# FPGA_PERIPHERALS.net
KiCad netlist of a schematic drawn in Altium Designer
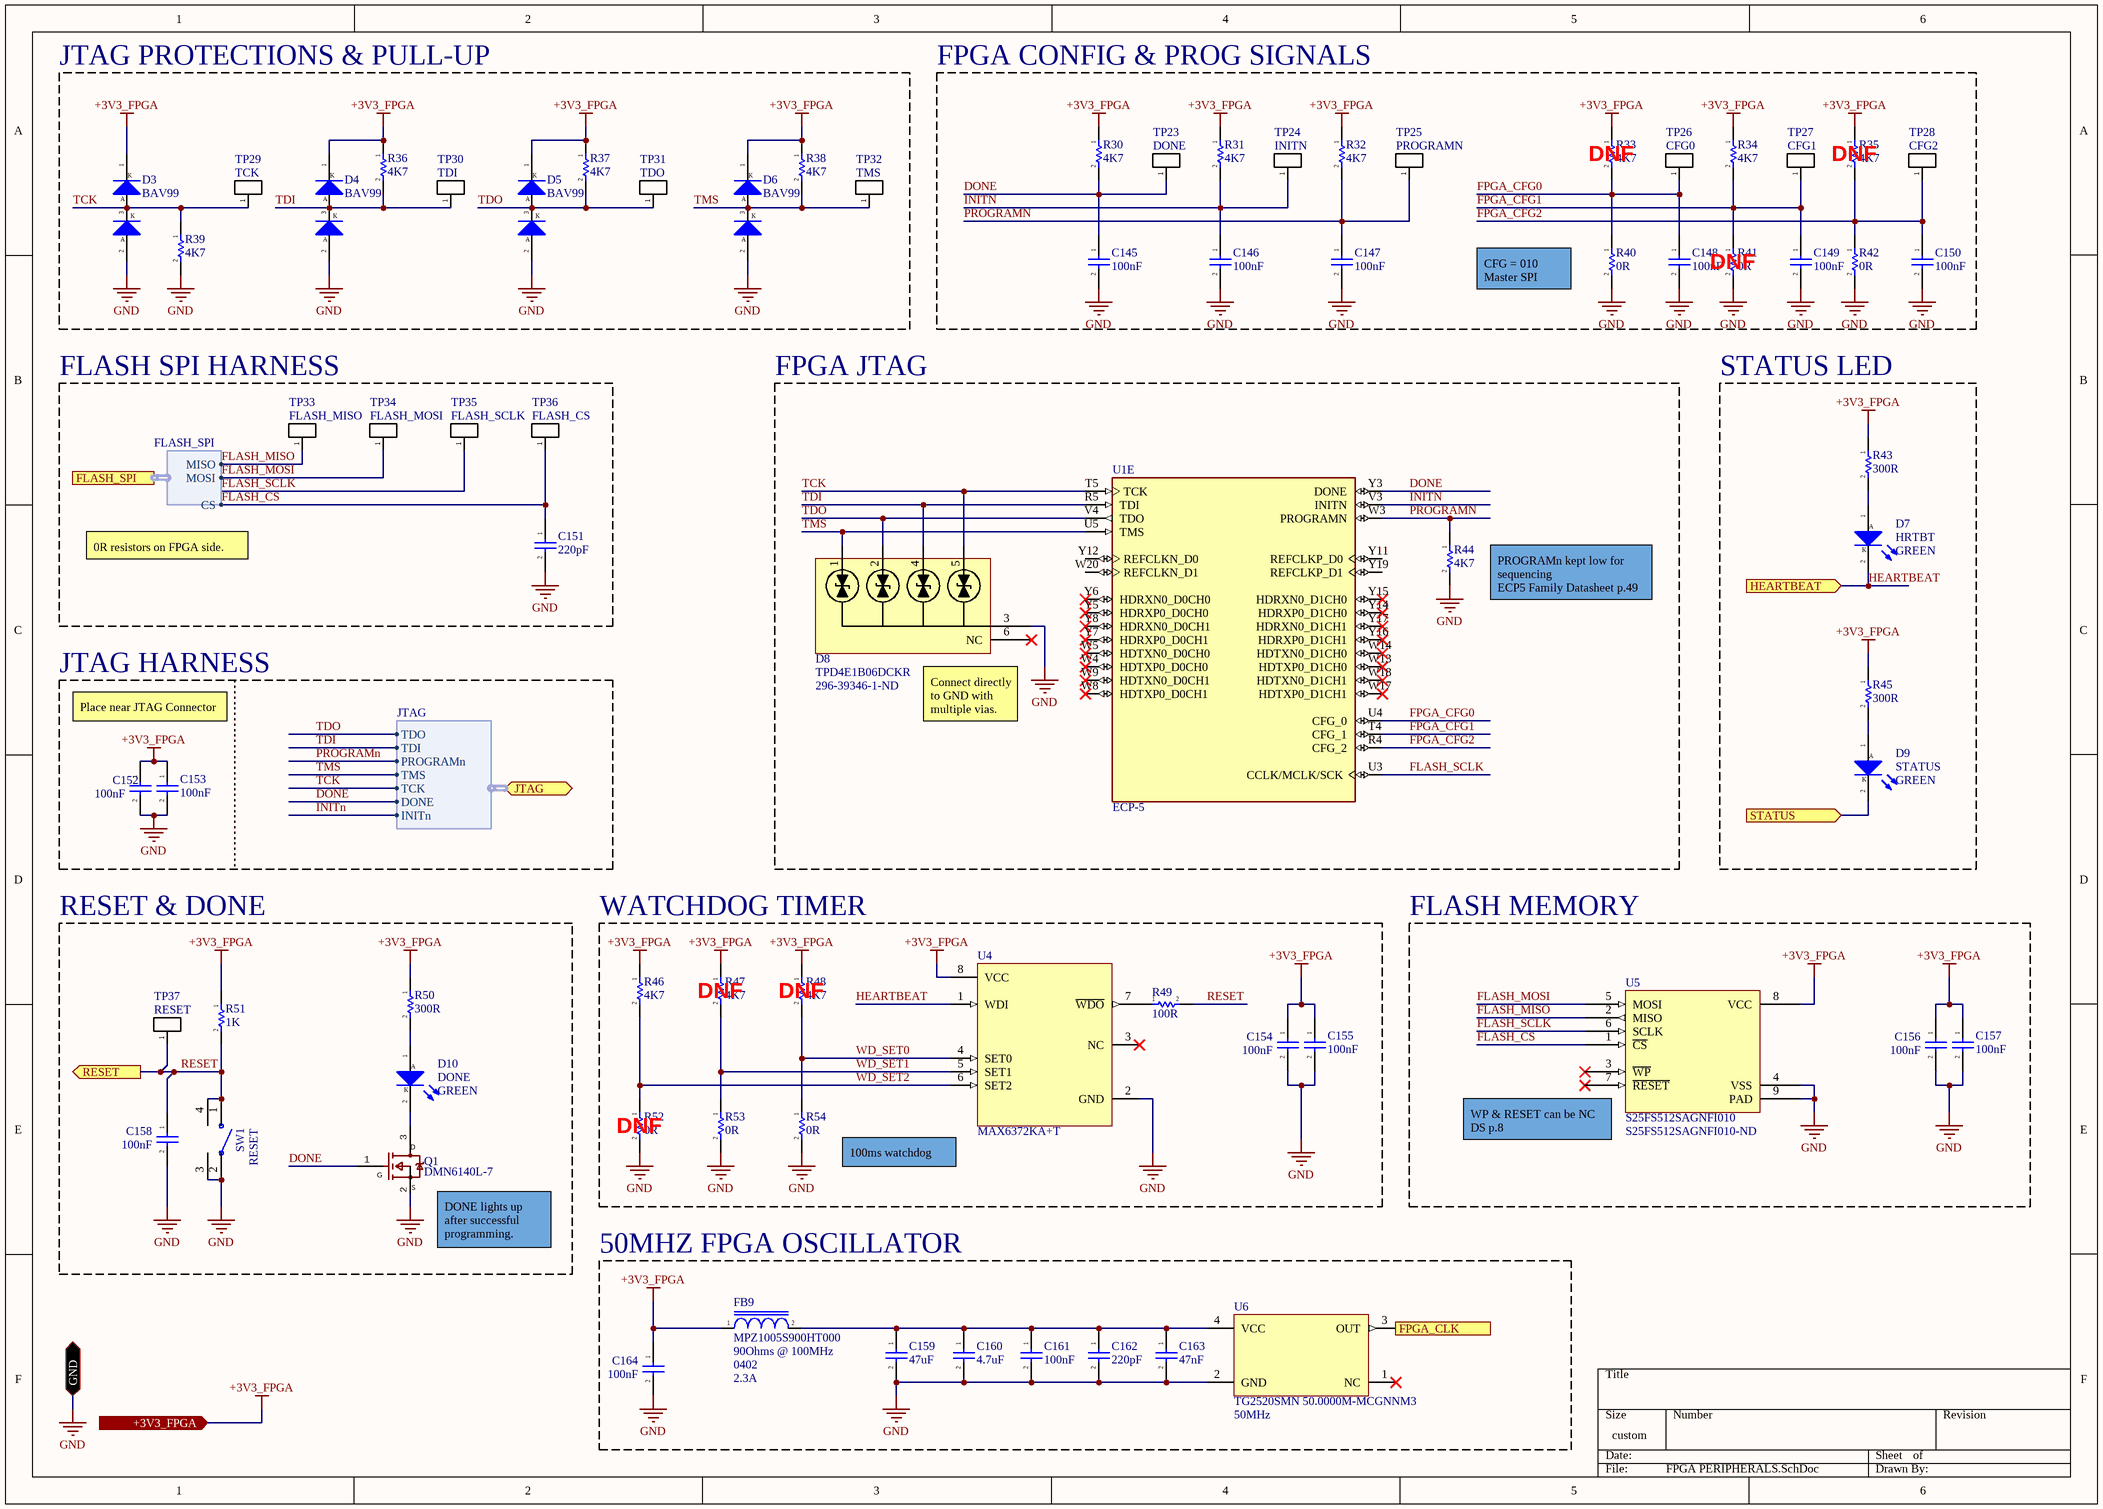
[diagram p0: FPGA PERIPHERALS.SchDoc]

(export (version "E")
  (design (tool "Eeschema 10.0.6"))
  (components
    (comp (ref "C145")
      (value "100nF")
      (footprint "CAP_0402")
      (description "Generic SMT Ceramic Capacitor")
      (libsource (lib "Symbols") (part "CAP_CER"))
    )
    (comp (ref "C146")
      (value "100nF")
      (footprint "CAP_0402")
      (description "Generic SMT Ceramic Capacitor")
      (libsource (lib "Symbols") (part "CAP_CER"))
    )
    (comp (ref "C147")
      (value "100nF")
      (footprint "CAP_0402")
      (description "Generic SMT Ceramic Capacitor")
      (libsource (lib "Symbols") (part "CAP_CER"))
    )
    (comp (ref "C148")
      (value "100nF")
      (footprint "CAP_0402")
      (description "Generic SMT Ceramic Capacitor")
      (libsource (lib "Symbols") (part "CAP_CER"))
    )
    (comp (ref "C149")
      (value "100nF")
      (footprint "CAP_0402")
      (description "Generic SMT Ceramic Capacitor")
      (libsource (lib "Symbols") (part "CAP_CER"))
    )
    (comp (ref "C150")
      (value "100nF")
      (footprint "CAP_0402")
      (description "Generic SMT Ceramic Capacitor")
      (libsource (lib "Symbols") (part "CAP_CER"))
    )
    (comp (ref "C151")
      (value "220pF")
      (footprint "CAP_0402")
      (description "Generic SMT Ceramic Capacitor")
      (libsource (lib "Symbols") (part "CAP_CER"))
    )
    (comp (ref "C152")
      (value "100nF")
      (footprint "CAP_0402")
      (description "Generic SMT Ceramic Capacitor")
      (libsource (lib "Symbols") (part "CAP_CER"))
    )
    (comp (ref "C153")
      (value "100nF")
      (footprint "CAP_0402")
      (description "Generic SMT Ceramic Capacitor")
      (libsource (lib "Symbols") (part "CAP_CER"))
    )
    (comp (ref "C154")
      (value "100nF")
      (footprint "CAP_0402")
      (description "Generic SMT Ceramic Capacitor")
      (libsource (lib "Symbols") (part "CAP_CER"))
    )
    (comp (ref "C155")
      (value "100nF")
      (footprint "CAP_0402")
      (description "Generic SMT Ceramic Capacitor")
      (libsource (lib "Symbols") (part "CAP_CER"))
    )
    (comp (ref "C156")
      (value "100nF")
      (footprint "CAP_0402")
      (description "Generic SMT Ceramic Capacitor")
      (libsource (lib "Symbols") (part "CAP_CER"))
    )
    (comp (ref "C157")
      (value "100nF")
      (footprint "CAP_0402")
      (description "Generic SMT Ceramic Capacitor")
      (libsource (lib "Symbols") (part "CAP_CER"))
    )
    (comp (ref "C158")
      (value "100nF")
      (footprint "CAP_0402")
      (description "Generic SMT Ceramic Capacitor")
      (libsource (lib "Symbols") (part "CAP_CER"))
    )
    (comp (ref "C159")
      (value "47uF")
      (footprint "CAP_1206")
      (description "Generic SMT Ceramic Capacitor")
      (libsource (lib "Symbols") (part "CAP_CER"))
    )
    (comp (ref "C160")
      (value "4.7uF")
      (footprint "CAP_0805")
      (description "Generic SMT Ceramic Capacitor")
      (libsource (lib "Symbols") (part "CAP_CER"))
    )
    (comp (ref "C161")
      (value "100nF")
      (footprint "CAP_0402")
      (description "Generic SMT Ceramic Capacitor")
      (libsource (lib "Symbols") (part "CAP_CER"))
    )
    (comp (ref "C162")
      (value "220pF")
      (footprint "CAP_0402")
      (description "Generic SMT Ceramic Capacitor")
      (libsource (lib "Symbols") (part "CAP_CER"))
    )
    (comp (ref "C163")
      (value "47nF")
      (footprint "CAP_0201")
      (description "Generic SMT Ceramic Capacitor")
      (libsource (lib "Symbols") (part "CAP_CER"))
    )
    (comp (ref "C164")
      (value "100nF")
      (footprint "CAP_0402")
      (description "Generic SMT Ceramic Capacitor")
      (libsource (lib "Symbols") (part "CAP_CER"))
    )
    (comp (ref "D3")
      (value "BAV99")
      (footprint "MMBD7000-7-F")
      (description "DIODE ARRAY GP 75V 300MA SOT23-3")
      (fields (field (name "MFR") "Taiwan Semiconductor Corporation"))
      (libsource (lib "CryptLib") (part "DIODE_BAV99"))
    )
    (comp (ref "D4")
      (value "BAV99")
      (footprint "MMBD7000-7-F")
      (description "DIODE ARRAY GP 75V 300MA SOT23-3")
      (fields (field (name "MFR") "Taiwan Semiconductor Corporation"))
      (libsource (lib "CryptLib") (part "DIODE_BAV99"))
    )
    (comp (ref "D5")
      (value "BAV99")
      (footprint "MMBD7000-7-F")
      (description "DIODE ARRAY GP 75V 300MA SOT23-3")
      (fields (field (name "MFR") "Taiwan Semiconductor Corporation"))
      (libsource (lib "CryptLib") (part "DIODE_BAV99"))
    )
    (comp (ref "D6")
      (value "BAV99")
      (footprint "MMBD7000-7-F")
      (description "DIODE ARRAY GP 75V 300MA SOT23-3")
      (fields (field (name "MFR") "Taiwan Semiconductor Corporation"))
      (libsource (lib "CryptLib") (part "DIODE_BAV99"))
    )
    (comp (ref "D7")
      (value "HRTBT")
      (footprint "LED_0402")
      (description "Generic LED")
      (fields (field (name "COLOR") "GREEN"))
      (libsource (lib "RaesLib") (part "DIODE_LED"))
    )
    (comp (ref "D8")
      (value "TPD4E1B06DCKR")
      (footprint "TPD4E1B06DCKR")
      (description "TVS DIODE 5.5VWM 14.5VC SC70-6")
      (fields
        (field (name "MFR") "Texas Instruments")
        (field (name "SUPPLIER PART NUMBER 1") "296-39346-1-ND")
      )
      (libsource (lib "CryptLib") (part "DIODE_TPD4E1B06DCKR"))
    )
    (comp (ref "D9")
      (value "STATUS")
      (footprint "LED_0402")
      (description "Generic LED")
      (fields (field (name "COLOR") "GREEN"))
      (libsource (lib "RaesLib") (part "DIODE_LED"))
    )
    (comp (ref "D10")
      (value "DONE")
      (footprint "LED_0402")
      (description "Generic LED")
      (fields (field (name "COLOR") "GREEN"))
      (libsource (lib "RaesLib") (part "DIODE_LED"))
    )
    (comp (ref "FB9")
      (value "MPZ1005S900HT000")
      (footprint "IND_0402")
      (description "90 Ohms @ 100 MHz 1 Power Line Ferrite Bead 0402 (1005 Metric) 2.3A 38mOhm")
      (fields
        (field (name "IMPEDANCE @ FREQ") "90Ohms @ 100MHz")
        (field (name "PACKAGE / CASE") "0402")
        (field (name "CURRENT RATING") "2.3A")
      )
      (libsource (lib "CryptLib") (part "IND_MPZ1005S900HT000"))
    )
    (comp (ref "Q1")
      (value "DMN6140L-7")
      (footprint "SOT23-3")
      (description "N-Channel 60 V 1.6A (Ta) 700mW (Ta) Surface Mount SOT-23")
      (fields (field (name "MFR") "Diodes Incorporated"))
      (libsource (lib "CryptLib") (part "TRANS_DMN6140L-7"))
    )
    (comp (ref "R30")
      (value "4K7")
      (footprint "RES_0603")
      (description "Resistor")
      (fields (field (name "POWER") "1/16W") (field (name "TOLERANCE") "10%"))
      (libsource (lib "Symbols") (part "RESISTOR"))
    )
    (comp (ref "R31")
      (value "4K7")
      (footprint "RES_0603")
      (description "Resistor")
      (fields (field (name "POWER") "1/16W") (field (name "TOLERANCE") "10%"))
      (libsource (lib "Symbols") (part "RESISTOR"))
    )
    (comp (ref "R32")
      (value "4K7")
      (footprint "RES_0603")
      (description "Resistor")
      (fields (field (name "POWER") "1/16W") (field (name "TOLERANCE") "10%"))
      (libsource (lib "Symbols") (part "RESISTOR"))
    )
    (comp (ref "R33")
      (value "4K7")
      (footprint "RES_0603")
      (description "Resistor")
      (fields (field (name "POWER") "1/16W") (field (name "TOLERANCE") "10%"))
      (libsource (lib "Symbols") (part "RESISTOR"))
    )
    (comp (ref "R34")
      (value "4K7")
      (footprint "RES_0603")
      (description "Resistor")
      (fields (field (name "POWER") "1/16W") (field (name "TOLERANCE") "10%"))
      (libsource (lib "Symbols") (part "RESISTOR"))
    )
    (comp (ref "R35")
      (value "4K7")
      (footprint "RES_0603")
      (description "Resistor")
      (fields (field (name "POWER") "1/16W") (field (name "TOLERANCE") "10%"))
      (libsource (lib "Symbols") (part "RESISTOR"))
    )
    (comp (ref "R36")
      (value "4K7")
      (footprint "RES_0603")
      (description "Resistor")
      (fields (field (name "POWER") "1/16W") (field (name "TOLERANCE") "10%"))
      (libsource (lib "Symbols") (part "RESISTOR"))
    )
    (comp (ref "R37")
      (value "4K7")
      (footprint "RES_0603")
      (description "Resistor")
      (fields (field (name "POWER") "1/16W") (field (name "TOLERANCE") "10%"))
      (libsource (lib "Symbols") (part "RESISTOR"))
    )
    (comp (ref "R38")
      (value "4K7")
      (footprint "RES_0603")
      (description "Resistor")
      (fields (field (name "POWER") "1/16W") (field (name "TOLERANCE") "10%"))
      (libsource (lib "Symbols") (part "RESISTOR"))
    )
    (comp (ref "R39")
      (value "4K7")
      (footprint "RES_0603")
      (description "Resistor")
      (fields (field (name "POWER") "1/16W") (field (name "TOLERANCE") "10%"))
      (libsource (lib "Symbols") (part "RESISTOR"))
    )
    (comp (ref "R40")
      (value "0R")
      (footprint "RES_0603")
      (description "Resistor")
      (fields (field (name "POWER") "1/8W") (field (name "TOLERANCE") "10%"))
      (libsource (lib "Symbols") (part "RESISTOR"))
    )
    (comp (ref "R41")
      (value "0R")
      (footprint "RES_0603")
      (description "Resistor")
      (fields (field (name "POWER") "1/8W") (field (name "TOLERANCE") "10%"))
      (libsource (lib "Symbols") (part "RESISTOR"))
    )
    (comp (ref "R42")
      (value "0R")
      (footprint "RES_0603")
      (description "Resistor")
      (fields (field (name "POWER") "1/8W") (field (name "TOLERANCE") "10%"))
      (libsource (lib "Symbols") (part "RESISTOR"))
    )
    (comp (ref "R43")
      (value "300R")
      (footprint "RES_0603")
      (description "Resistor")
      (fields (field (name "POWER") "1/8W") (field (name "TOLERANCE") "2%"))
      (libsource (lib "Symbols") (part "RESISTOR"))
    )
    (comp (ref "R44")
      (value "4K7")
      (footprint "RES_0603")
      (description "Resistor")
      (fields (field (name "POWER") "1/16W") (field (name "TOLERANCE") "10%"))
      (libsource (lib "Symbols") (part "RESISTOR"))
    )
    (comp (ref "R45")
      (value "300R")
      (footprint "RES_0603")
      (description "Resistor")
      (fields (field (name "POWER") "1/8W") (field (name "TOLERANCE") "2%"))
      (libsource (lib "Symbols") (part "RESISTOR"))
    )
    (comp (ref "R46")
      (value "4K7")
      (footprint "RES_0603")
      (description "Resistor")
      (fields (field (name "POWER") "1/16W") (field (name "TOLERANCE") "10%"))
      (libsource (lib "Symbols") (part "RESISTOR"))
    )
    (comp (ref "R47")
      (value "4K7")
      (footprint "RES_0603")
      (description "Resistor")
      (fields (field (name "POWER") "1/16W") (field (name "TOLERANCE") "10%"))
      (libsource (lib "Symbols") (part "RESISTOR"))
    )
    (comp (ref "R48")
      (value "4K7")
      (footprint "RES_0603")
      (description "Resistor")
      (fields (field (name "POWER") "1/16W") (field (name "TOLERANCE") "10%"))
      (libsource (lib "Symbols") (part "RESISTOR"))
    )
    (comp (ref "R49")
      (value "100R")
      (footprint "RES_0402")
      (description "Resistor")
      (fields (field (name "POWER") "1/8W") (field (name "TOLERANCE") "10%"))
      (libsource (lib "Symbols") (part "RESISTOR"))
    )
    (comp (ref "R50")
      (value "300R")
      (footprint "RES_0603")
      (description "Resistor")
      (fields (field (name "POWER") "1/8W") (field (name "TOLERANCE") "2%"))
      (libsource (lib "Symbols") (part "RESISTOR"))
    )
    (comp (ref "R51")
      (value "1K")
      (footprint "RES_0603")
      (description "Resistor")
      (fields (field (name "POWER") "1/8W") (field (name "TOLERANCE") "5%"))
      (libsource (lib "Symbols") (part "RESISTOR"))
    )
    (comp (ref "R52")
      (value "0R")
      (footprint "RES_0603")
      (description "Resistor")
      (fields (field (name "POWER") "1/8W") (field (name "TOLERANCE") "10%"))
      (libsource (lib "Symbols") (part "RESISTOR"))
    )
    (comp (ref "R53")
      (value "0R")
      (footprint "RES_0603")
      (description "Resistor")
      (fields (field (name "POWER") "1/8W") (field (name "TOLERANCE") "10%"))
      (libsource (lib "Symbols") (part "RESISTOR"))
    )
    (comp (ref "R54")
      (value "0R")
      (footprint "RES_0603")
      (description "Resistor")
      (fields (field (name "POWER") "1/8W") (field (name "TOLERANCE") "10%"))
      (libsource (lib "Symbols") (part "RESISTOR"))
    )
    (comp (ref "SW1")
      (value "RESET")
      (footprint "KMR621NGLFS")
      (description "Tactile Switch SPST-NO Top Actuated Surface Mount")
      (fields (field (name "MFR") "C&K") (field (name "ALTERNATIVE PART") "KMR641NG ULC LFS"))
      (libsource (lib "CryptLib") (part "SW_KMR621NG_LFS"))
    )
    (comp (ref "TP23")
      (value "DONE")
      (footprint "TP_PAD_TINY")
      (description "Test Point")
      (libsource (lib "Symbols") (part "TESTPOINT"))
    )
    (comp (ref "TP24")
      (value "INITN")
      (footprint "TP_PAD_TINY")
      (description "Test Point")
      (libsource (lib "Symbols") (part "TESTPOINT"))
    )
    (comp (ref "TP25")
      (value "PROGRAMN")
      (footprint "TP_PAD_TINY")
      (description "Test Point")
      (libsource (lib "Symbols") (part "TESTPOINT"))
    )
    (comp (ref "TP26")
      (value "CFG0")
      (footprint "TP_PAD_TINY")
      (description "Test Point")
      (libsource (lib "Symbols") (part "TESTPOINT"))
    )
    (comp (ref "TP27")
      (value "CFG1")
      (footprint "TP_PAD_TINY")
      (description "Test Point")
      (libsource (lib "Symbols") (part "TESTPOINT"))
    )
    (comp (ref "TP28")
      (value "CFG2")
      (footprint "TP_PAD_TINY")
      (description "Test Point")
      (libsource (lib "Symbols") (part "TESTPOINT"))
    )
    (comp (ref "TP29")
      (value "TCK")
      (footprint "TP_PAD_SMALL")
      (description "Test Point")
      (libsource (lib "Symbols") (part "TESTPOINT"))
    )
    (comp (ref "TP30")
      (value "TDI")
      (footprint "TP_PAD_SMALL")
      (description "Test Point")
      (libsource (lib "Symbols") (part "TESTPOINT"))
    )
    (comp (ref "TP31")
      (value "TDO")
      (footprint "TP_PAD_SMALL")
      (description "Test Point")
      (libsource (lib "Symbols") (part "TESTPOINT"))
    )
    (comp (ref "TP32")
      (value "TMS")
      (footprint "TP_PAD_SMALL")
      (description "Test Point")
      (libsource (lib "Symbols") (part "TESTPOINT"))
    )
    (comp (ref "TP33")
      (value "FLASH_MISO")
      (footprint "TP_PAD_SMALL")
      (description "Test Point")
      (libsource (lib "Symbols") (part "TESTPOINT"))
    )
    (comp (ref "TP34")
      (value "FLASH_MOSI")
      (footprint "TP_PAD_SMALL")
      (description "Test Point")
      (libsource (lib "Symbols") (part "TESTPOINT"))
    )
    (comp (ref "TP35")
      (value "FLASH_SCLK")
      (footprint "TP_PAD_SMALL")
      (description "Test Point")
      (libsource (lib "Symbols") (part "TESTPOINT"))
    )
    (comp (ref "TP36")
      (value "FLASH_CS")
      (footprint "TP_PAD_SMALL")
      (description "Test Point")
      (libsource (lib "Symbols") (part "TESTPOINT"))
    )
    (comp (ref "TP37")
      (value "RESET")
      (footprint "TP_PAD_SMALL")
      (description "Test Point")
      (libsource (lib "Symbols") (part "TESTPOINT"))
    )
    (comp (ref "U1")
      (value "ECP-5")
      (footprint "CryptLib:CABGA-381")
      (description "IC FPGA 203 I/O 381CABGA")
      (fields (field (name "MFR") "Lattice Semiconductors"))
      (libsource (lib "CryptLib") (part "IC_LFE5UM-45F-8BG381C"))
    )
    (comp (ref "U4")
      (value "MAX6372KA+T")
      (footprint "SOT23-8")
      (description "Watchdog Push-Pull, Totem Pole 1 Channel SOT-23-8")
      (fields (field (name "MFR") "Maxim Integrated"))
      (libsource (lib "CryptLib") (part "IC_MAX6372KA-T"))
    )
    (comp (ref "U5")
      (value "S25FS512SAGNFI010")
      (footprint "s25FL256LAGNFV010")
      (description "FLASH - NOR Memory IC 512Mb (64M x 8) SPI - Quad I/O, QPI 133 MHz 8-WSON (6x8)")
      (fields (field (name "MFR") "Cypress") (field (name "SUPPLIER PART NUMBER 1") "S25FS512SAGNFI010-ND"))
      (libsource (lib "CryptLib") (part "IC_S25FS512SAGNFI010"))
    )
    (comp (ref "U6")
      (value "TG2520SMN 50.0000M-MCGNNM3")
      (footprint "TG2520SMN")
      (description "50 MHz TCXO Clipped Sine Wave Oscillator 2.8V ~ 3.3V - 4-SMD, No Lead")
      (fields (field (name "MFR") "EPSON") (field (name "FREQUENCY") "50MHz"))
      (libsource (lib "CryptLib") (part "IC_TG2520SMN_50.0000M-MCGNNM3"))
    )
  )
  (nets
    (net (code "3") (name "+3V3_FPGA") (class "Default")
      (node (ref "C152") (pin "1") (pinfunction "1_1") (pintype "passive"))
      (node (ref "C153") (pin "1") (pinfunction "1_1") (pintype "passive"))
      (node (ref "C154") (pin "1") (pinfunction "1_1") (pintype "passive"))
      (node (ref "C155") (pin "1") (pinfunction "1_1") (pintype "passive"))
      (node (ref "C156") (pin "1") (pinfunction "1_1") (pintype "passive"))
      (node (ref "C157") (pin "1") (pinfunction "1_1") (pintype "passive"))
      (node (ref "C164") (pin "1") (pinfunction "1_1") (pintype "passive"))
      (node (ref "D3") (pin "1") (pinfunction "K_1") (pintype "passive"))
      (node (ref "D4") (pin "1") (pinfunction "K_1") (pintype "passive"))
      (node (ref "D5") (pin "1") (pinfunction "K_1") (pintype "passive"))
      (node (ref "D6") (pin "1") (pinfunction "K_1") (pintype "passive"))
      (node (ref "FB9") (pin "1") (pinfunction "1_1") (pintype "passive"))
      (node (ref "R30") (pin "1") (pinfunction "1_1") (pintype "passive"))
      (node (ref "R31") (pin "1") (pinfunction "1_1") (pintype "passive"))
      (node (ref "R32") (pin "1") (pinfunction "1_1") (pintype "passive"))
      (node (ref "R33") (pin "1") (pinfunction "1_1") (pintype "passive"))
      (node (ref "R34") (pin "1") (pinfunction "1_1") (pintype "passive"))
      (node (ref "R35") (pin "1") (pinfunction "1_1") (pintype "passive"))
      (node (ref "R36") (pin "1") (pinfunction "1_1") (pintype "passive"))
      (node (ref "R37") (pin "1") (pinfunction "1_1") (pintype "passive"))
      (node (ref "R38") (pin "1") (pinfunction "1_1") (pintype "passive"))
      (node (ref "R43") (pin "1") (pinfunction "1_1") (pintype "passive"))
      (node (ref "R45") (pin "1") (pinfunction "1_1") (pintype "passive"))
      (node (ref "R46") (pin "1") (pinfunction "1_1") (pintype "passive"))
      (node (ref "R47") (pin "1") (pinfunction "1_1") (pintype "passive"))
      (node (ref "R48") (pin "1") (pinfunction "1_1") (pintype "passive"))
      (node (ref "R50") (pin "1") (pinfunction "1_1") (pintype "passive"))
      (node (ref "R51") (pin "1") (pinfunction "1_1") (pintype "passive"))
      (node (ref "U4") (pin "8") (pinfunction "VCC_8") (pintype "power_in"))
      (node (ref "U5") (pin "8") (pinfunction "VCC_8") (pintype "power_in"))
    )
    (net (code "4") (name "/DONE") (class "Default")
      (node (ref "C145") (pin "1") (pinfunction "1_1") (pintype "passive"))
      (node (ref "Q1") (pin "1") (pintype "passive"))
      (node (ref "R30") (pin "2") (pinfunction "2_2") (pintype "passive"))
      (node (ref "TP23") (pin "1") (pinfunction "A_1") (pintype "passive"))
      (node (ref "U1") (pin "Y3") (pinfunction "DONE_Y3") (pintype "bidirectional"))
    )
    (net (code "5") (name "/FLASH_CS") (class "Default")
      (node (ref "C151") (pin "1") (pinfunction "1_1") (pintype "passive"))
      (node (ref "TP36") (pin "1") (pinfunction "A_1") (pintype "passive"))
      (node (ref "U5") (pin "1") (pinfunction "~{CS}_1") (pintype "input"))
    )
    (net (code "6") (name "/FLASH_MISO") (class "Default")
      (node (ref "TP33") (pin "1") (pinfunction "A_1") (pintype "passive"))
      (node (ref "U5") (pin "2") (pinfunction "MISO_2") (pintype "output"))
    )
    (net (code "7") (name "/FLASH_MOSI") (class "Default")
      (node (ref "TP34") (pin "1") (pinfunction "A_1") (pintype "passive"))
      (node (ref "U5") (pin "5") (pinfunction "MOSI_5") (pintype "input"))
    )
    (net (code "8") (name "/FLASH_SCLK") (class "Default")
      (node (ref "TP35") (pin "1") (pinfunction "A_1") (pintype "passive"))
      (node (ref "U1") (pin "U3") (pinfunction "CCLK/MCLK/SCK_U3") (pintype "bidirectional"))
      (node (ref "U5") (pin "6") (pinfunction "SCLK_6") (pintype "input"))
    )
    (net (code "9") (name "/FPGA_CFG0") (class "Default")
      (node (ref "C148") (pin "1") (pinfunction "1_1") (pintype "passive"))
      (node (ref "R33") (pin "2") (pinfunction "2_2") (pintype "passive"))
      (node (ref "R40") (pin "1") (pinfunction "1_1") (pintype "passive"))
      (node (ref "TP26") (pin "1") (pinfunction "A_1") (pintype "passive"))
      (node (ref "U1") (pin "U4") (pinfunction "CFG_0_U4") (pintype "bidirectional"))
    )
    (net (code "10") (name "/FPGA_CFG1") (class "Default")
      (node (ref "C149") (pin "1") (pinfunction "1_1") (pintype "passive"))
      (node (ref "R34") (pin "2") (pinfunction "2_2") (pintype "passive"))
      (node (ref "R41") (pin "1") (pinfunction "1_1") (pintype "passive"))
      (node (ref "TP27") (pin "1") (pinfunction "A_1") (pintype "passive"))
      (node (ref "U1") (pin "T4") (pinfunction "CFG_1_T4") (pintype "bidirectional"))
    )
    (net (code "11") (name "/FPGA_CFG2") (class "Default")
      (node (ref "C150") (pin "1") (pinfunction "1_1") (pintype "passive"))
      (node (ref "R35") (pin "2") (pinfunction "2_2") (pintype "passive"))
      (node (ref "R42") (pin "1") (pinfunction "1_1") (pintype "passive"))
      (node (ref "TP28") (pin "1") (pinfunction "A_1") (pintype "passive"))
      (node (ref "U1") (pin "R4") (pinfunction "CFG_2_R4") (pintype "bidirectional"))
    )
    (net (code "12") (name "/FPGA_CLK") (class "Default")
      (node (ref "U6") (pin "3") (pinfunction "OUT_3") (pintype "output"))
    )
    (net (code "13") (name "/HEARTBEAT") (class "Default")
      (node (ref "D7") (pin "2") (pinfunction "K_2") (pintype "passive"))
      (node (ref "U4") (pin "1") (pinfunction "WDI_1") (pintype "input"))
    )
    (net (code "14") (name "/INITN") (class "Default")
      (node (ref "C146") (pin "1") (pinfunction "1_1") (pintype "passive"))
      (node (ref "R31") (pin "2") (pinfunction "2_2") (pintype "passive"))
      (node (ref "TP24") (pin "1") (pinfunction "A_1") (pintype "passive"))
      (node (ref "U1") (pin "V3") (pinfunction "INITN_V3") (pintype "bidirectional"))
    )
    (net (code "16") (name "/PROGRAMN") (class "Default")
      (node (ref "C147") (pin "1") (pinfunction "1_1") (pintype "passive"))
      (node (ref "R32") (pin "2") (pinfunction "2_2") (pintype "passive"))
      (node (ref "R44") (pin "1") (pinfunction "1_1") (pintype "passive"))
      (node (ref "TP25") (pin "1") (pinfunction "A_1") (pintype "passive"))
      (node (ref "U1") (pin "W3") (pinfunction "PROGRAMN_W3") (pintype "bidirectional"))
    )
    (net (code "18") (name "/RESET") (class "Default")
      (node (ref "C158") (pin "1") (pinfunction "1_1") (pintype "passive"))
      (node (ref "R49") (pin "2") (pinfunction "2_2") (pintype "passive"))
      (node (ref "R51") (pin "2") (pinfunction "2_2") (pintype "passive"))
      (node (ref "SW1") (pin "1") (pinfunction "1_1") (pintype "passive"))
      (node (ref "SW1") (pin "4") (pinfunction "1_4") (pintype "passive"))
      (node (ref "TP37") (pin "1") (pinfunction "A_1") (pintype "passive"))
    )
    (net (code "19") (name "/STATUS") (class "Default")
      (node (ref "D9") (pin "2") (pinfunction "K_2") (pintype "passive"))
    )
    (net (code "20") (name "/TCK") (class "Default")
      (node (ref "D3") (pin "3") (pinfunction "A_3") (pintype "passive"))
      (node (ref "D8") (pin "5") (pinfunction "A_5") (pintype "passive"))
      (node (ref "R39") (pin "1") (pinfunction "1_1") (pintype "passive"))
      (node (ref "TP29") (pin "1") (pinfunction "A_1") (pintype "passive"))
      (node (ref "U1") (pin "T5") (pinfunction "TCK_T5") (pintype "input"))
    )
    (net (code "21") (name "/TDI") (class "Default")
      (node (ref "D4") (pin "3") (pinfunction "A_3") (pintype "passive"))
      (node (ref "D8") (pin "4") (pinfunction "A_4") (pintype "passive"))
      (node (ref "R36") (pin "2") (pinfunction "2_2") (pintype "passive"))
      (node (ref "TP30") (pin "1") (pinfunction "A_1") (pintype "passive"))
      (node (ref "U1") (pin "R5") (pinfunction "TDI_R5") (pintype "input"))
    )
    (net (code "22") (name "/TDO") (class "Default")
      (node (ref "D5") (pin "3") (pinfunction "A_3") (pintype "passive"))
      (node (ref "D8") (pin "2") (pinfunction "A_2") (pintype "passive"))
      (node (ref "R37") (pin "2") (pinfunction "2_2") (pintype "passive"))
      (node (ref "TP31") (pin "1") (pinfunction "A_1") (pintype "passive"))
      (node (ref "U1") (pin "V4") (pinfunction "TDO_V4") (pintype "output"))
    )
    (net (code "23") (name "/TMS") (class "Default")
      (node (ref "D6") (pin "3") (pinfunction "A_3") (pintype "passive"))
      (node (ref "D8") (pin "1") (pinfunction "A_1") (pintype "passive"))
      (node (ref "R38") (pin "2") (pinfunction "2_2") (pintype "passive"))
      (node (ref "TP32") (pin "1") (pinfunction "A_1") (pintype "passive"))
      (node (ref "U1") (pin "U5") (pinfunction "TMS_U5") (pintype "input"))
    )
    (net (code "24") (name "/WD_SET0") (class "Default")
      (node (ref "R48") (pin "2") (pinfunction "2_2") (pintype "passive"))
      (node (ref "R54") (pin "1") (pinfunction "1_1") (pintype "passive"))
      (node (ref "U4") (pin "4") (pinfunction "SET0_4") (pintype "input"))
    )
    (net (code "25") (name "/WD_SET1") (class "Default")
      (node (ref "R47") (pin "2") (pinfunction "2_2") (pintype "passive"))
      (node (ref "R53") (pin "1") (pinfunction "1_1") (pintype "passive"))
      (node (ref "U4") (pin "5") (pinfunction "SET1_5") (pintype "input"))
    )
    (net (code "26") (name "/WD_SET2") (class "Default")
      (node (ref "R46") (pin "2") (pinfunction "2_2") (pintype "passive"))
      (node (ref "R52") (pin "1") (pinfunction "1_1") (pintype "passive"))
      (node (ref "U4") (pin "6") (pinfunction "SET2_6") (pintype "input"))
    )
    (net (code "29") (name "GND") (class "Default")
      (node (ref "C145") (pin "2") (pinfunction "2_2") (pintype "passive"))
      (node (ref "C146") (pin "2") (pinfunction "2_2") (pintype "passive"))
      (node (ref "C147") (pin "2") (pinfunction "2_2") (pintype "passive"))
      (node (ref "C148") (pin "2") (pinfunction "2_2") (pintype "passive"))
      (node (ref "C149") (pin "2") (pinfunction "2_2") (pintype "passive"))
      (node (ref "C150") (pin "2") (pinfunction "2_2") (pintype "passive"))
      (node (ref "C151") (pin "2") (pinfunction "2_2") (pintype "passive"))
      (node (ref "C152") (pin "2") (pinfunction "2_2") (pintype "passive"))
      (node (ref "C153") (pin "2") (pinfunction "2_2") (pintype "passive"))
      (node (ref "C154") (pin "2") (pinfunction "2_2") (pintype "passive"))
      (node (ref "C155") (pin "2") (pinfunction "2_2") (pintype "passive"))
      (node (ref "C156") (pin "2") (pinfunction "2_2") (pintype "passive"))
      (node (ref "C157") (pin "2") (pinfunction "2_2") (pintype "passive"))
      (node (ref "C158") (pin "2") (pinfunction "2_2") (pintype "passive"))
      (node (ref "C159") (pin "2") (pinfunction "2_2") (pintype "passive"))
      (node (ref "C160") (pin "2") (pinfunction "2_2") (pintype "passive"))
      (node (ref "C161") (pin "2") (pinfunction "2_2") (pintype "passive"))
      (node (ref "C162") (pin "2") (pinfunction "2_2") (pintype "passive"))
      (node (ref "C163") (pin "2") (pinfunction "2_2") (pintype "passive"))
      (node (ref "C164") (pin "2") (pinfunction "2_2") (pintype "passive"))
      (node (ref "D3") (pin "2") (pinfunction "K_2") (pintype "passive"))
      (node (ref "D4") (pin "2") (pinfunction "K_2") (pintype "passive"))
      (node (ref "D5") (pin "2") (pinfunction "K_2") (pintype "passive"))
      (node (ref "D6") (pin "2") (pinfunction "K_2") (pintype "passive"))
      (node (ref "D8") (pin "3") (pinfunction "GND_3") (pintype "passive"))
      (node (ref "Q1") (pin "2") (pintype "passive"))
      (node (ref "R39") (pin "2") (pinfunction "2_2") (pintype "passive"))
      (node (ref "R40") (pin "2") (pinfunction "2_2") (pintype "passive"))
      (node (ref "R41") (pin "2") (pinfunction "2_2") (pintype "passive"))
      (node (ref "R42") (pin "2") (pinfunction "2_2") (pintype "passive"))
      (node (ref "R44") (pin "2") (pinfunction "2_2") (pintype "passive"))
      (node (ref "R52") (pin "2") (pinfunction "2_2") (pintype "passive"))
      (node (ref "R53") (pin "2") (pinfunction "2_2") (pintype "passive"))
      (node (ref "R54") (pin "2") (pinfunction "2_2") (pintype "passive"))
      (node (ref "SW1") (pin "2") (pinfunction "2_2") (pintype "passive"))
      (node (ref "SW1") (pin "3") (pinfunction "2_3") (pintype "passive"))
      (node (ref "U4") (pin "2") (pinfunction "GND_2") (pintype "power_in"))
      (node (ref "U5") (pin "4") (pinfunction "VSS_4") (pintype "power_in"))
      (node (ref "U5") (pin "9") (pinfunction "PAD_9") (pintype "power_in"))
      (node (ref "U6") (pin "2") (pinfunction "GND_2") (pintype "power_in"))
    )
    (net (code "30") (name "Net-(D7-A)") (class "Default")
      (node (ref "D7") (pin "1") (pinfunction "A_1") (pintype "passive"))
      (node (ref "R43") (pin "2") (pinfunction "2_2") (pintype "passive"))
    )
    (net (code "31") (name "Net-(D9-A)") (class "Default")
      (node (ref "D9") (pin "1") (pinfunction "A_1") (pintype "passive"))
      (node (ref "R45") (pin "2") (pinfunction "2_2") (pintype "passive"))
    )
    (net (code "32") (name "Net-(D10-A)") (class "Default")
      (node (ref "D10") (pin "1") (pinfunction "A_1") (pintype "passive"))
      (node (ref "R50") (pin "2") (pinfunction "2_2") (pintype "passive"))
    )
    (net (code "33") (name "Net-(D10-K)") (class "Default")
      (node (ref "D10") (pin "2") (pinfunction "K_2") (pintype "passive"))
      (node (ref "Q1") (pin "3") (pintype "passive"))
    )
    (net (code "34") (name "Net-(U4-~{WDO})") (class "Default")
      (node (ref "R49") (pin "1") (pinfunction "1_1") (pintype "passive"))
      (node (ref "U4") (pin "7") (pinfunction "~{WDO}_7") (pintype "output"))
    )
    (net (code "35") (name "Net-(U6-VCC)") (class "Default")
      (node (ref "C159") (pin "1") (pinfunction "1_1") (pintype "passive"))
      (node (ref "C160") (pin "1") (pinfunction "1_1") (pintype "passive"))
      (node (ref "C161") (pin "1") (pinfunction "1_1") (pintype "passive"))
      (node (ref "C162") (pin "1") (pinfunction "1_1") (pintype "passive"))
      (node (ref "C163") (pin "1") (pinfunction "1_1") (pintype "passive"))
      (node (ref "FB9") (pin "2") (pinfunction "2_2") (pintype "passive"))
      (node (ref "U6") (pin "4") (pinfunction "VCC_4") (pintype "power_in"))
    )
    (net (code "36") (name "unconnected-(D8-NC-Pad6)") (class "Default")
      (node (ref "D8") (pin "6") (pinfunction "NC_6") (pintype "passive+no_connect"))
    )
    (net (code "37") (name "unconnected-(U1E-HDRXN0_D0CH0-PadY6)") (class "Default")
      (node (ref "U1") (pin "Y6") (pinfunction "HDRXN0_D0CH0_Y6") (pintype "bidirectional+no_connect"))
    )
    (net (code "38") (name "unconnected-(U1E-HDRXN0_D0CH1-PadY8)") (class "Default")
      (node (ref "U1") (pin "Y8") (pinfunction "HDRXN0_D0CH1_Y8") (pintype "bidirectional+no_connect"))
    )
    (net (code "39") (name "unconnected-(U1E-HDRXN0_D1CH0-PadY15)") (class "Default")
      (node (ref "U1") (pin "Y15") (pinfunction "HDRXN0_D1CH0_Y15") (pintype "bidirectional+no_connect"))
    )
    (net (code "40") (name "unconnected-(U1E-HDRXN0_D1CH1-PadY17)") (class "Default")
      (node (ref "U1") (pin "Y17") (pinfunction "HDRXN0_D1CH1_Y17") (pintype "bidirectional+no_connect"))
    )
    (net (code "41") (name "unconnected-(U1E-HDRXP0_D0CH0-PadY5)") (class "Default")
      (node (ref "U1") (pin "Y5") (pinfunction "HDRXP0_D0CH0_Y5") (pintype "bidirectional+no_connect"))
    )
    (net (code "42") (name "unconnected-(U1E-HDRXP0_D0CH1-PadY7)") (class "Default")
      (node (ref "U1") (pin "Y7") (pinfunction "HDRXP0_D0CH1_Y7") (pintype "bidirectional+no_connect"))
    )
    (net (code "43") (name "unconnected-(U1E-HDRXP0_D1CH0-PadY14)") (class "Default")
      (node (ref "U1") (pin "Y14") (pinfunction "HDRXP0_D1CH0_Y14") (pintype "bidirectional+no_connect"))
    )
    (net (code "44") (name "unconnected-(U1E-HDRXP0_D1CH1-PadY16)") (class "Default")
      (node (ref "U1") (pin "Y16") (pinfunction "HDRXP0_D1CH1_Y16") (pintype "bidirectional+no_connect"))
    )
    (net (code "45") (name "unconnected-(U1E-HDTXN0_D0CH0-PadW5)") (class "Default")
      (node (ref "U1") (pin "W5") (pinfunction "HDTXN0_D0CH0_W5") (pintype "bidirectional+no_connect"))
    )
    (net (code "46") (name "unconnected-(U1E-HDTXN0_D0CH1-PadW9)") (class "Default")
      (node (ref "U1") (pin "W9") (pinfunction "HDTXN0_D0CH1_W9") (pintype "bidirectional+no_connect"))
    )
    (net (code "47") (name "unconnected-(U1E-HDTXN0_D1CH0-PadW14)") (class "Default")
      (node (ref "U1") (pin "W14") (pinfunction "HDTXN0_D1CH0_W14") (pintype "bidirectional+no_connect"))
    )
    (net (code "48") (name "unconnected-(U1E-HDTXN0_D1CH1-PadW18)") (class "Default")
      (node (ref "U1") (pin "W18") (pinfunction "HDTXN0_D1CH1_W18") (pintype "bidirectional+no_connect"))
    )
    (net (code "49") (name "unconnected-(U1E-HDTXP0_D0CH0-PadW4)") (class "Default")
      (node (ref "U1") (pin "W4") (pinfunction "HDTXP0_D0CH0_W4") (pintype "bidirectional+no_connect"))
    )
    (net (code "50") (name "unconnected-(U1E-HDTXP0_D0CH1-PadW8)") (class "Default")
      (node (ref "U1") (pin "W8") (pinfunction "HDTXP0_D0CH1_W8") (pintype "bidirectional+no_connect"))
    )
    (net (code "51") (name "unconnected-(U1E-HDTXP0_D1CH0-PadW13)") (class "Default")
      (node (ref "U1") (pin "W13") (pinfunction "HDTXP0_D1CH0_W13") (pintype "bidirectional+no_connect"))
    )
    (net (code "52") (name "unconnected-(U1E-HDTXP0_D1CH1-PadW17)") (class "Default")
      (node (ref "U1") (pin "W17") (pinfunction "HDTXP0_D1CH1_W17") (pintype "bidirectional+no_connect"))
    )
    (net (code "53") (name "unconnected-(U1E-REFCLKN_D0-PadY12)") (class "Default")
      (node (ref "U1") (pin "Y12") (pinfunction "REFCLKN_D0_Y12") (pintype "bidirectional"))
    )
    (net (code "54") (name "unconnected-(U1E-REFCLKN_D1-PadW20)") (class "Default")
      (node (ref "U1") (pin "W20") (pinfunction "REFCLKN_D1_W20") (pintype "bidirectional"))
    )
    (net (code "55") (name "unconnected-(U1E-REFCLKP_D0-PadY11)") (class "Default")
      (node (ref "U1") (pin "Y11") (pinfunction "REFCLKP_D0_Y11") (pintype "bidirectional"))
    )
    (net (code "56") (name "unconnected-(U1E-REFCLKP_D1-PadY19)") (class "Default")
      (node (ref "U1") (pin "Y19") (pinfunction "REFCLKP_D1_Y19") (pintype "bidirectional"))
    )
    (net (code "57") (name "unconnected-(U4-NC-Pad3)") (class "Default")
      (node (ref "U4") (pin "3") (pinfunction "NC_3") (pintype "passive+no_connect"))
    )
    (net (code "58") (name "unconnected-(U5-~{RESET}-Pad7)") (class "Default")
      (node (ref "U5") (pin "7") (pinfunction "~{RESET}_7") (pintype "input+no_connect"))
    )
    (net (code "59") (name "unconnected-(U5-~{WP}-Pad3)") (class "Default")
      (node (ref "U5") (pin "3") (pinfunction "~{WP}_3") (pintype "input+no_connect"))
    )
    (net (code "60") (name "unconnected-(U6-NC-Pad1)") (class "Default")
      (node (ref "U6") (pin "1") (pinfunction "NC_1") (pintype "passive+no_connect"))
    )
  )
)
